# PowerSequence.net
KiCad netlist of a schematic drawn in Altium Designer
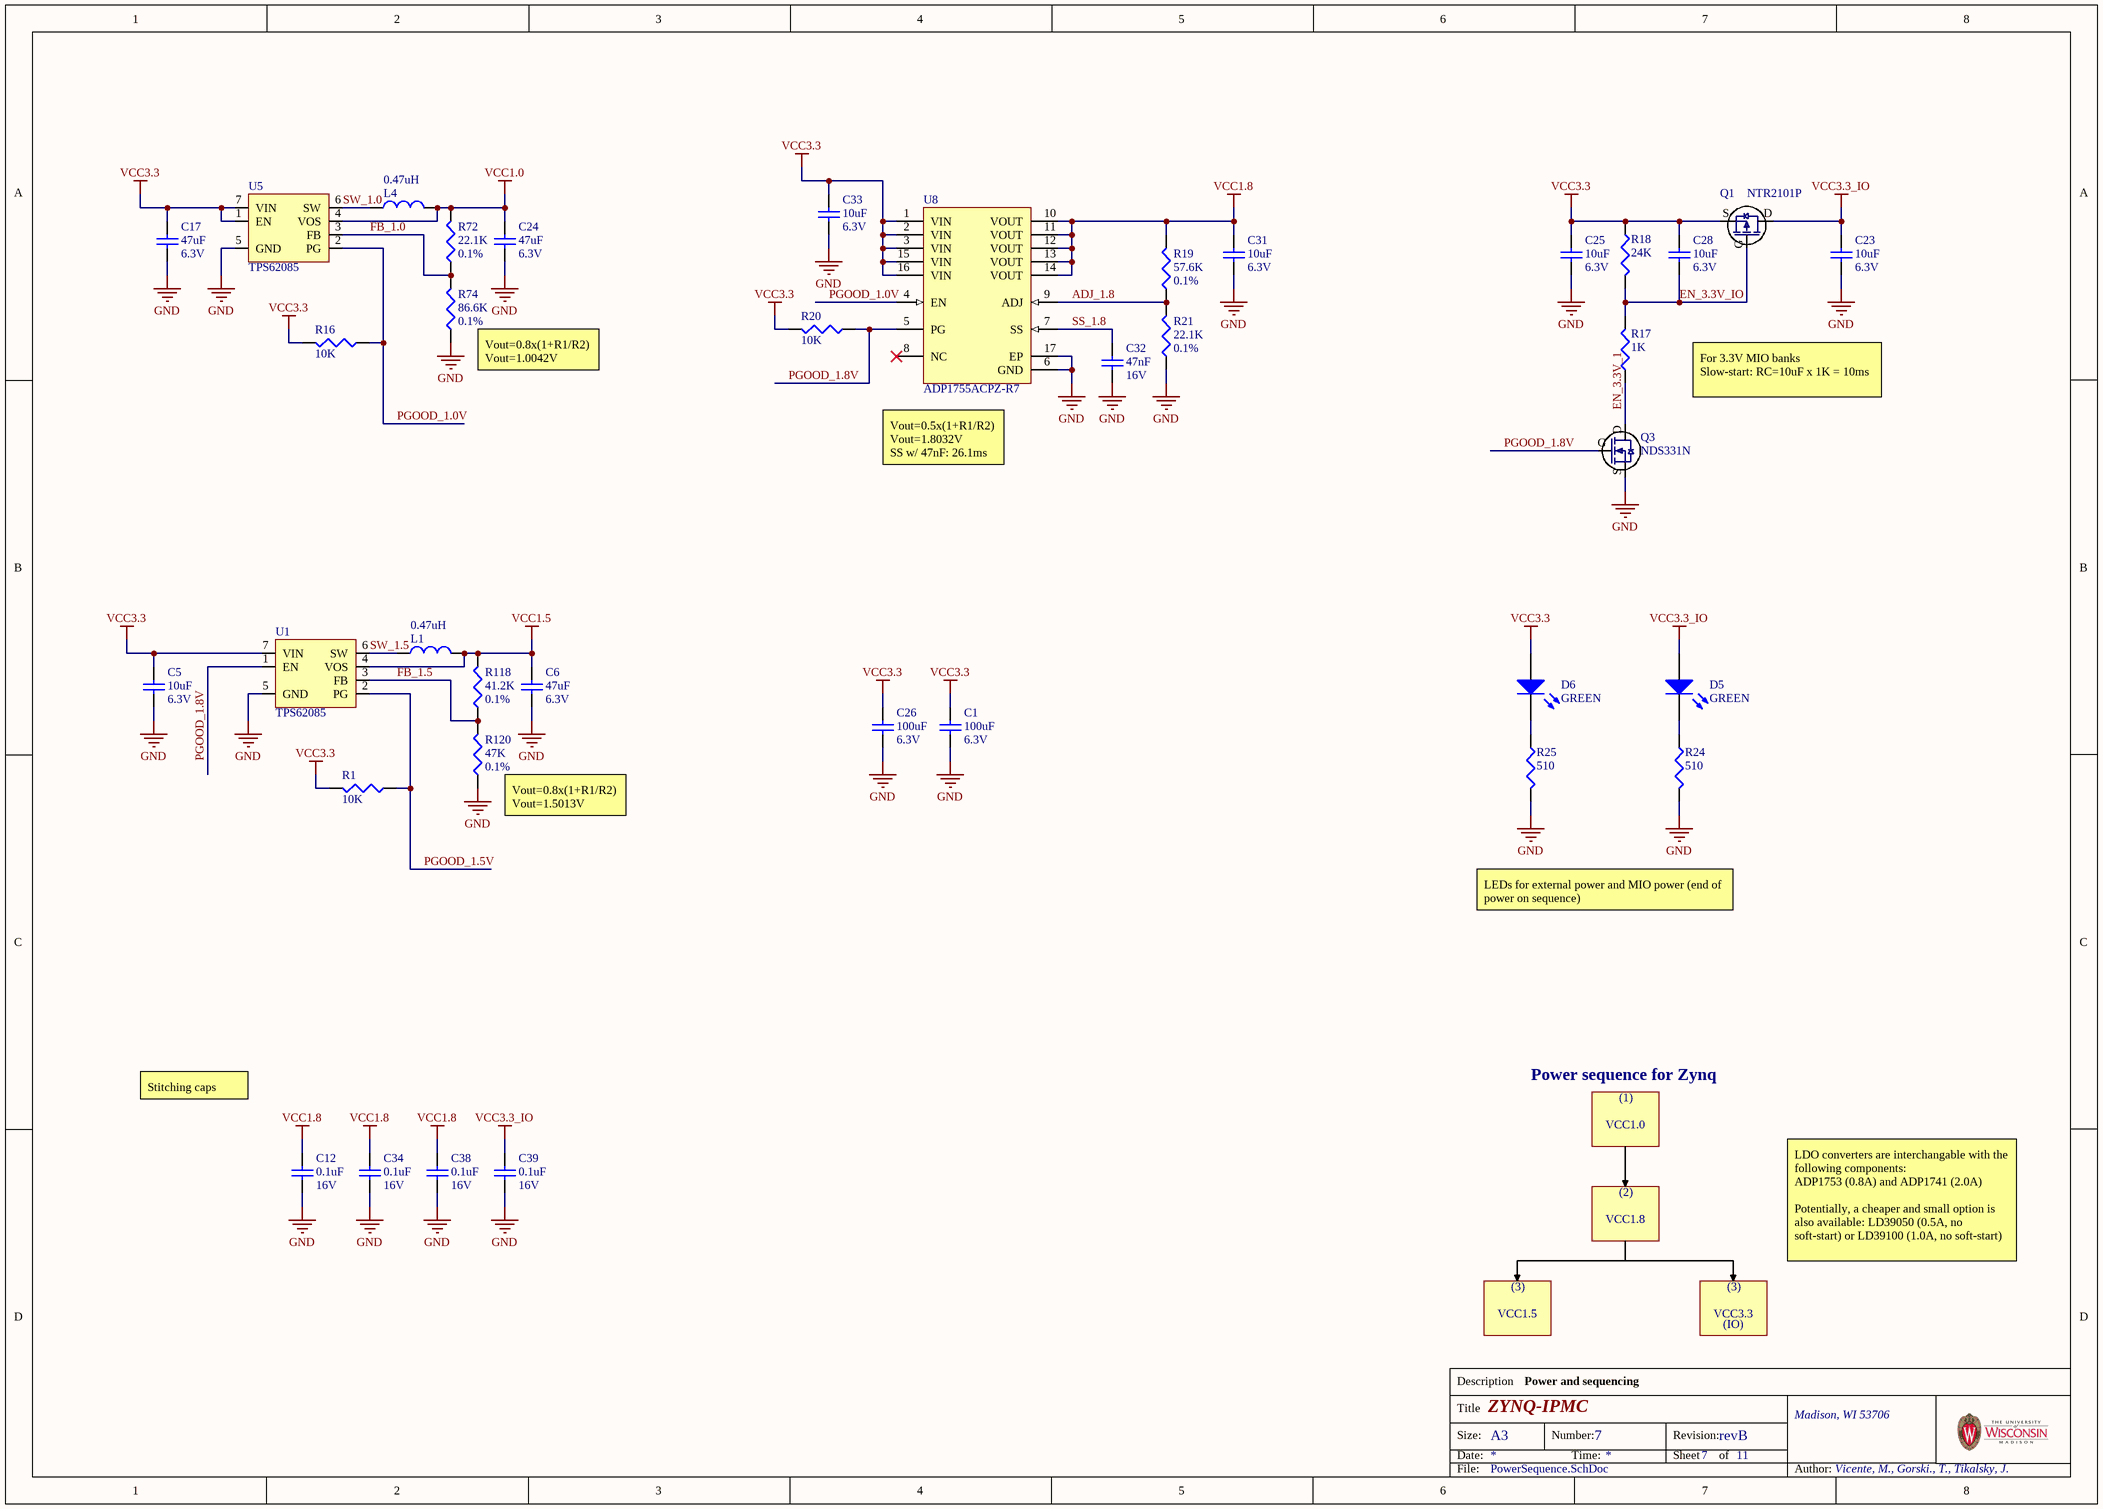
[diagram p0: PowerSequence.SchDoc]

(export (version "E")
  (design (tool "Eeschema 10.0.6"))
  (components
    (comp (ref "C1")
      (value "100uF")
      (footprint "C1210_IPC_H")
      (description "Capacitor")
      (fields
        (field (name "RATING") "6.3V")
        (field (name "PART") "GRM32ER60J107ME20L")
        (field (name "MANUFACTURER") "Murata")
      )
      (libsource (lib "CustomParts") (part "Cap"))
    )
    (comp (ref "C5")
      (value "10uF")
      (footprint "C0402_IPC_H")
      (description "Capacitor")
      (fields
        (field (name "RATING") "6.3V")
        (field (name "MANUFACTURER") "Murata")
        (field (name "PART") "GRM155R60J106ME44D")
      )
      (libsource (lib "CustomParts") (part "Cap"))
    )
    (comp (ref "C6")
      (value "47uF")
      (footprint "C0805_M")
      (description "Capacitor")
      (fields
        (field (name "RATING") "6.3V")
        (field (name "MANUFACTURER") "TDK")
        (field (name "PART") "C2012X5R0J476M125AC")
      )
      (libsource (lib "CustomParts") (part "Cap"))
    )
    (comp (ref "C12")
      (value "0.1uF")
      (footprint "C0402_IPC_H")
      (description "Capacitor")
      (fields
        (field (name "RATING") "16V")
        (field (name "MANUFACTURER") "Murata")
        (field (name "PART") "GRM155R71C104KA88D")
      )
      (libsource (lib "CustomParts") (part "Cap"))
    )
    (comp (ref "C17")
      (value "47uF")
      (footprint "C0805_M")
      (description "Capacitor")
      (fields
        (field (name "RATING") "6.3V")
        (field (name "MANUFACTURER") "TDK")
        (field (name "PART") "C2012X5R0J476M125AC")
      )
      (libsource (lib "CustomParts") (part "Cap"))
    )
    (comp (ref "C23")
      (value "10uF")
      (footprint "C0402_IPC_H")
      (description "Capacitor")
      (fields
        (field (name "RATING") "6.3V")
        (field (name "MANUFACTURER") "Murata")
        (field (name "PART") "GRM155R60J106ME44D")
      )
      (libsource (lib "CustomParts") (part "Cap"))
    )
    (comp (ref "C24")
      (value "47uF")
      (footprint "C0805_M")
      (description "Capacitor")
      (fields
        (field (name "RATING") "6.3V")
        (field (name "MANUFACTURER") "TDK")
        (field (name "PART") "C2012X5R0J476M125AC")
      )
      (libsource (lib "CustomParts") (part "Cap"))
    )
    (comp (ref "C25")
      (value "10uF")
      (footprint "C0402_IPC_H")
      (description "Capacitor")
      (fields
        (field (name "RATING") "6.3V")
        (field (name "MANUFACTURER") "Murata")
        (field (name "PART") "GRM155R60J106ME44D")
      )
      (libsource (lib "CustomParts") (part "Cap"))
    )
    (comp (ref "C26")
      (value "100uF")
      (footprint "C1210_IPC_H")
      (description "Capacitor")
      (fields
        (field (name "RATING") "6.3V")
        (field (name "PART") "GRM32ER60J107ME20L")
        (field (name "MANUFACTURER") "Murata")
      )
      (libsource (lib "CustomParts") (part "Cap"))
    )
    (comp (ref "C28")
      (value "10uF")
      (footprint "C0402_IPC_H")
      (description "Capacitor")
      (fields
        (field (name "RATING") "6.3V")
        (field (name "MANUFACTURER") "Murata")
        (field (name "PART") "GRM155R60J106ME44D")
      )
      (libsource (lib "CustomParts") (part "Cap"))
    )
    (comp (ref "C31")
      (value "10uF")
      (footprint "C0402_IPC_H")
      (description "Capacitor")
      (fields
        (field (name "RATING") "6.3V")
        (field (name "MANUFACTURER") "Murata")
        (field (name "PART") "GRM155R60J106ME44D")
      )
      (libsource (lib "CustomParts") (part "Cap"))
    )
    (comp (ref "C32")
      (value "47nF")
      (footprint "C0402_IPC_H")
      (description "Capacitor")
      (fields
        (field (name "RATING") "16V")
        (field (name "PART") "GRM155R71C473KA01D")
        (field (name "MANUFACTURER") "Murata")
      )
      (libsource (lib "CustomParts") (part "Cap"))
    )
    (comp (ref "C33")
      (value "10uF")
      (footprint "C0402_IPC_H")
      (description "Capacitor")
      (fields
        (field (name "RATING") "6.3V")
        (field (name "MANUFACTURER") "Murata")
        (field (name "PART") "GRM155R60J106ME44D")
      )
      (libsource (lib "CustomParts") (part "Cap"))
    )
    (comp (ref "C34")
      (value "0.1uF")
      (footprint "C0402_IPC_H")
      (description "Capacitor")
      (fields
        (field (name "RATING") "16V")
        (field (name "MANUFACTURER") "Murata")
        (field (name "PART") "GRM155R71C104KA88D")
      )
      (libsource (lib "CustomParts") (part "Cap"))
    )
    (comp (ref "C38")
      (value "0.1uF")
      (footprint "C0402_IPC_H")
      (description "Capacitor")
      (fields
        (field (name "RATING") "16V")
        (field (name "MANUFACTURER") "Murata")
        (field (name "PART") "GRM155R71C104KA88D")
      )
      (libsource (lib "CustomParts") (part "Cap"))
    )
    (comp (ref "C39")
      (value "0.1uF")
      (footprint "C0402_IPC_H")
      (description "Capacitor")
      (fields
        (field (name "RATING") "16V")
        (field (name "MANUFACTURER") "Murata")
        (field (name "PART") "GRM155R71C104KA88D")
      )
      (libsource (lib "CustomParts") (part "Cap"))
    )
    (comp (ref "D5")
      (value "GREEN")
      (footprint "LED0603_M")
      (description "Light Emitting Diode")
      (fields (field (name "MANUFACTURER") "Lite-On") (field (name "PART") "LTST-C190KGKT"))
      (libsource (lib "CustomParts") (part "LED"))
    )
    (comp (ref "D6")
      (value "GREEN")
      (footprint "LED0603_M")
      (description "Light Emitting Diode")
      (fields (field (name "MANUFACTURER") "Lite-On") (field (name "PART") "LTST-C190KGKT"))
      (libsource (lib "CustomParts") (part "LED"))
    )
    (comp (ref "L1")
      (value "0.47uH")
      (footprint "L2520_H")
      (description "Inductor")
      (fields (field (name "TOLERANCE") "20%") (field (name "MANUFACTURER") "Murata"))
      (libsource (lib "CustomParts") (part "Ind"))
    )
    (comp (ref "L4")
      (value "0.47uH")
      (footprint "L2520_H")
      (description "Inductor")
      (fields (field (name "TOLERANCE") "20%") (field (name "MANUFACTURER") "Murata"))
      (libsource (lib "CustomParts") (part "Ind"))
    )
    (comp (ref "Q1")
      (value "NTR2101P")
      (footprint "SOT23-H")
      (description "Small Signal MOSFET, −8.0V, −3.7 A, Single P−Channel, SOT−23")
      (fields (field (name "MANUFACTURER") "On Semiconductor"))
      (libsource (lib "CustomParts") (part "NTR2101P"))
    )
    (comp (ref "Q3")
      (value "NDS331N")
      (footprint "SOT23-H")
      (description "N-Channel   Logic Level Enhancement Mode Field Effect Transistor")
      (fields (field (name "MANUFACTURER") "Fairchild"))
      (libsource (lib "CustomParts") (part "NDS331N"))
    )
    (comp (ref "R1")
      (value "10K")
      (footprint "R0201_IPC_H")
      (description "Resistor")
      (fields (field (name "TOLERANCE") "1%") (field (name "MANUFACTURER") "Panasonic"))
      (libsource (lib "CustomParts") (part "Res"))
    )
    (comp (ref "R16")
      (value "10K")
      (footprint "R0201_IPC_H")
      (description "Resistor")
      (fields (field (name "TOLERANCE") "1%") (field (name "MANUFACTURER") "Panasonic"))
      (libsource (lib "CustomParts") (part "Res"))
    )
    (comp (ref "R17")
      (value "1K")
      (footprint "R0402_IPC_H")
      (description "Resistor")
      (fields (field (name "TOLERANCE") "1%") (field (name "MANUFACTURER") "Panasonic-ECG"))
      (libsource (lib "CustomParts") (part "Res"))
    )
    (comp (ref "R18")
      (value "24K")
      (footprint "R0402_IPC_H")
      (description "Resistor")
      (fields (field (name "TOLERANCE") "1%") (field (name "MANUFACTURER") "Panasonic"))
      (libsource (lib "CustomParts") (part "Res"))
    )
    (comp (ref "R19")
      (value "57.6K")
      (footprint "R0402_IPC_H")
      (description "Resistor")
      (fields
        (field (name "TOLERANCE") "0.1%")
        (field (name "MANUFACTURER") "Panasonic")
        (field (name "PART") "ERA-2AEB5762X")
      )
      (libsource (lib "CustomParts") (part "Res"))
    )
    (comp (ref "R20")
      (value "10K")
      (footprint "R0201_IPC_H")
      (description "Resistor")
      (fields (field (name "TOLERANCE") "1%") (field (name "MANUFACTURER") "Panasonic"))
      (libsource (lib "CustomParts") (part "Res"))
    )
    (comp (ref "R21")
      (value "22.1K")
      (footprint "R0402_IPC_H")
      (description "Resistor")
      (fields
        (field (name "TOLERANCE") "0.1%")
        (field (name "MANUFACTURER") "Panasonic")
        (field (name "PART") "ERA-2AEB2212X")
      )
      (libsource (lib "CustomParts") (part "Res"))
    )
    (comp (ref "R24")
      (value "510")
      (footprint "R0402_IPC_H")
      (description "Resistor")
      (fields (field (name "TOLERANCE") "1%") (field (name "MANUFACTURER") "Panasonic-ECG"))
      (libsource (lib "CustomParts") (part "Res"))
    )
    (comp (ref "R25")
      (value "510")
      (footprint "R0402_IPC_H")
      (description "Resistor")
      (fields (field (name "TOLERANCE") "1%") (field (name "MANUFACTURER") "Panasonic-ECG"))
      (libsource (lib "CustomParts") (part "Res"))
    )
    (comp (ref "R72")
      (value "22.1K")
      (footprint "R0402_IPC_H")
      (description "Resistor")
      (fields
        (field (name "TOLERANCE") "0.1%")
        (field (name "MANUFACTURER") "Panasonic")
        (field (name "PART") "ERA-2AEB2212X")
      )
      (libsource (lib "CustomParts") (part "Res"))
    )
    (comp (ref "R74")
      (value "86.6K")
      (footprint "R0402_IPC_H")
      (description "Resistor")
      (fields
        (field (name "TOLERANCE") "0.1%")
        (field (name "MANUFACTURER") "Panasonic-ECG")
        (field (name "PART") "ERA-2AEB8662X")
      )
      (libsource (lib "CustomParts") (part "Res"))
    )
    (comp (ref "R118")
      (value "41.2K")
      (footprint "R0402_IPC_H")
      (description "Resistor")
      (fields
        (field (name "TOLERANCE") "0.1%")
        (field (name "MANUFACTURER") "Panasonic")
        (field (name "PART") "ERA-2AEB4122X")
      )
      (libsource (lib "CustomParts") (part "Res"))
    )
    (comp (ref "R120")
      (value "47K")
      (footprint "R0402_IPC_H")
      (description "Resistor")
      (fields
        (field (name "TOLERANCE") "0.1%")
        (field (name "MANUFACTURER") "Panasonic")
        (field (name "PART") "ERA-2AEB473X")
      )
      (libsource (lib "CustomParts") (part "Res"))
    )
    (comp (ref "U1")
      (value "TPS62085")
      (footprint "VSON-8_L")
      (description "3-A Step-Down Converter With Hiccup Short-Circuit Protection")
      (fields (field (name "MANUFACTURER") "Texas Instruments"))
      (libsource (lib "CustomParts") (part "TPS62085"))
    )
    (comp (ref "U5")
      (value "TPS62085")
      (footprint "VSON-8_L")
      (description "3-A Step-Down Converter With Hiccup Short-Circuit Protection")
      (fields (field (name "MANUFACTURER") "Texas Instruments"))
      (libsource (lib "CustomParts") (part "TPS62085"))
    )
    (comp (ref "U8")
      (value "ADP1755ACPZ-R7")
      (footprint "CP-16-4_L")
      (fields (field (name "MANUFACTURER") "Analog"))
      (libsource (lib "altium-import") (part "root_0_ADI-ADP1755-CP-16-4_"))
    )
  )
  (nets
    (net (code "1") (name "/ADJ_1.8") (class "Default")
      (node (ref "R19") (pin "1") (pinfunction "1_1") (pintype "passive"))
      (node (ref "R21") (pin "2") (pinfunction "2_2") (pintype "passive"))
      (node (ref "U8") (pin "9") (pinfunction "ADJ_9") (pintype "input"))
    )
    (net (code "2") (name "/EN_3.3V_1") (class "Default")
      (node (ref "Q3") (pin "D") (pinfunction "D_D") (pintype "passive"))
      (node (ref "R17") (pin "1") (pinfunction "1_1") (pintype "passive"))
    )
    (net (code "3") (name "/EN_3.3V_IO") (class "Default")
      (node (ref "C28") (pin "2") (pinfunction "2_2") (pintype "passive"))
      (node (ref "Q1") (pin "G") (pinfunction "G_G") (pintype "passive"))
      (node (ref "R17") (pin "2") (pinfunction "2_2") (pintype "passive"))
      (node (ref "R18") (pin "2") (pinfunction "2_2") (pintype "passive"))
    )
    (net (code "4") (name "/FB_1.0") (class "Default")
      (node (ref "R72") (pin "1") (pinfunction "1_1") (pintype "passive"))
      (node (ref "R74") (pin "2") (pinfunction "2_2") (pintype "passive"))
      (node (ref "U5") (pin "3") (pinfunction "FB_3") (pintype "passive"))
    )
    (net (code "5") (name "/FB_1.5") (class "Default")
      (node (ref "R118") (pin "1") (pinfunction "1_1") (pintype "passive"))
      (node (ref "R120") (pin "2") (pinfunction "2_2") (pintype "passive"))
      (node (ref "U1") (pin "3") (pinfunction "FB_3") (pintype "passive"))
    )
    (net (code "6") (name "/PGOOD_1.0V") (class "Default")
      (node (ref "R16") (pin "1") (pinfunction "1_1") (pintype "passive"))
      (node (ref "U5") (pin "2") (pinfunction "PG_2") (pintype "passive"))
      (node (ref "U8") (pin "4") (pinfunction "EN_4") (pintype "input"))
    )
    (net (code "7") (name "/PGOOD_1.5V") (class "Default")
      (node (ref "R1") (pin "1") (pinfunction "1_1") (pintype "passive"))
      (node (ref "U1") (pin "2") (pinfunction "PG_2") (pintype "passive"))
    )
    (net (code "8") (name "/PGOOD_1.8V") (class "Default")
      (node (ref "Q3") (pin "G") (pinfunction "G_G") (pintype "passive"))
      (node (ref "R20") (pin "1") (pinfunction "1_1") (pintype "passive"))
      (node (ref "U1") (pin "1") (pinfunction "EN_1") (pintype "passive"))
      (node (ref "U8") (pin "5") (pinfunction "PG_5") (pintype "open_collector"))
    )
    (net (code "9") (name "/SS_1.8") (class "Default")
      (node (ref "C32") (pin "1") (pinfunction "1_1") (pintype "passive"))
      (node (ref "U8") (pin "7") (pinfunction "SS_7") (pintype "input"))
    )
    (net (code "10") (name "/SW_1.0") (class "Default")
      (node (ref "L4") (pin "1") (pinfunction "1_1") (pintype "passive"))
      (node (ref "U5") (pin "6") (pinfunction "SW_6") (pintype "passive"))
    )
    (net (code "11") (name "/SW_1.5") (class "Default")
      (node (ref "L1") (pin "1") (pinfunction "1_1") (pintype "passive"))
      (node (ref "U1") (pin "6") (pinfunction "SW_6") (pintype "passive"))
    )
    (net (code "12") (name "GND") (class "Default")
      (node (ref "C1") (pin "2") (pinfunction "2_2") (pintype "passive"))
      (node (ref "C12") (pin "2") (pinfunction "2_2") (pintype "passive"))
      (node (ref "C17") (pin "2") (pinfunction "2_2") (pintype "passive"))
      (node (ref "C23") (pin "2") (pinfunction "2_2") (pintype "passive"))
      (node (ref "C24") (pin "1") (pinfunction "1_1") (pintype "passive"))
      (node (ref "C25") (pin "2") (pinfunction "2_2") (pintype "passive"))
      (node (ref "C26") (pin "2") (pinfunction "2_2") (pintype "passive"))
      (node (ref "C31") (pin "1") (pinfunction "1_1") (pintype "passive"))
      (node (ref "C32") (pin "2") (pinfunction "2_2") (pintype "passive"))
      (node (ref "C33") (pin "2") (pinfunction "2_2") (pintype "passive"))
      (node (ref "C34") (pin "2") (pinfunction "2_2") (pintype "passive"))
      (node (ref "C38") (pin "2") (pinfunction "2_2") (pintype "passive"))
      (node (ref "C39") (pin "2") (pinfunction "2_2") (pintype "passive"))
      (node (ref "C5") (pin "2") (pinfunction "2_2") (pintype "passive"))
      (node (ref "C6") (pin "1") (pinfunction "1_1") (pintype "passive"))
      (node (ref "Q3") (pin "S") (pinfunction "S_S") (pintype "passive"))
      (node (ref "R120") (pin "1") (pinfunction "1_1") (pintype "passive"))
      (node (ref "R21") (pin "1") (pinfunction "1_1") (pintype "passive"))
      (node (ref "R24") (pin "2") (pinfunction "2_2") (pintype "passive"))
      (node (ref "R25") (pin "2") (pinfunction "2_2") (pintype "passive"))
      (node (ref "R74") (pin "1") (pinfunction "1_1") (pintype "passive"))
      (node (ref "U1") (pin "5") (pinfunction "GND_5") (pintype "passive"))
      (node (ref "U5") (pin "5") (pinfunction "GND_5") (pintype "passive"))
      (node (ref "U8") (pin "17") (pinfunction "EP_17") (pintype "power_in"))
      (node (ref "U8") (pin "6") (pinfunction "GND_6") (pintype "power_in"))
    )
    (net (code "13") (name "Net-(D5-K)") (class "Default")
      (node (ref "D5") (pin "2") (pinfunction "K_2") (pintype "passive"))
      (node (ref "R24") (pin "1") (pinfunction "1_1") (pintype "passive"))
    )
    (net (code "14") (name "Net-(D6-K)") (class "Default")
      (node (ref "D6") (pin "2") (pinfunction "K_2") (pintype "passive"))
      (node (ref "R25") (pin "1") (pinfunction "1_1") (pintype "passive"))
    )
    (net (code "15") (name "VCC1.0") (class "Default")
      (node (ref "C24") (pin "2") (pinfunction "2_2") (pintype "passive"))
      (node (ref "L4") (pin "2") (pinfunction "2_2") (pintype "passive"))
      (node (ref "R72") (pin "2") (pinfunction "2_2") (pintype "passive"))
      (node (ref "U5") (pin "4") (pinfunction "VOS_4") (pintype "passive"))
    )
    (net (code "16") (name "VCC1.5") (class "Default")
      (node (ref "C6") (pin "2") (pinfunction "2_2") (pintype "passive"))
      (node (ref "L1") (pin "2") (pinfunction "2_2") (pintype "passive"))
      (node (ref "R118") (pin "2") (pinfunction "2_2") (pintype "passive"))
      (node (ref "U1") (pin "4") (pinfunction "VOS_4") (pintype "passive"))
    )
    (net (code "17") (name "VCC1.8") (class "Default")
      (node (ref "C12") (pin "1") (pinfunction "1_1") (pintype "passive"))
      (node (ref "C31") (pin "2") (pinfunction "2_2") (pintype "passive"))
      (node (ref "C34") (pin "1") (pinfunction "1_1") (pintype "passive"))
      (node (ref "C38") (pin "1") (pinfunction "1_1") (pintype "passive"))
      (node (ref "R19") (pin "2") (pinfunction "2_2") (pintype "passive"))
      (node (ref "U8") (pin "10") (pinfunction "VOUT_10") (pintype "power_in"))
      (node (ref "U8") (pin "11") (pinfunction "VOUT_11") (pintype "power_in"))
      (node (ref "U8") (pin "12") (pinfunction "VOUT_12") (pintype "power_in"))
      (node (ref "U8") (pin "13") (pinfunction "VOUT_13") (pintype "power_in"))
      (node (ref "U8") (pin "14") (pinfunction "VOUT_14") (pintype "power_in"))
    )
    (net (code "18") (name "VCC3.3") (class "Default")
      (node (ref "C1") (pin "1") (pinfunction "1_1") (pintype "passive"))
      (node (ref "C17") (pin "1") (pinfunction "1_1") (pintype "passive"))
      (node (ref "C25") (pin "1") (pinfunction "1_1") (pintype "passive"))
      (node (ref "C26") (pin "1") (pinfunction "1_1") (pintype "passive"))
      (node (ref "C28") (pin "1") (pinfunction "1_1") (pintype "passive"))
      (node (ref "C33") (pin "1") (pinfunction "1_1") (pintype "passive"))
      (node (ref "C5") (pin "1") (pinfunction "1_1") (pintype "passive"))
      (node (ref "D6") (pin "1") (pinfunction "A_1") (pintype "passive"))
      (node (ref "Q1") (pin "S") (pinfunction "S_S") (pintype "passive"))
      (node (ref "R1") (pin "2") (pinfunction "2_2") (pintype "passive"))
      (node (ref "R16") (pin "2") (pinfunction "2_2") (pintype "passive"))
      (node (ref "R18") (pin "1") (pinfunction "1_1") (pintype "passive"))
      (node (ref "R20") (pin "2") (pinfunction "2_2") (pintype "passive"))
      (node (ref "U1") (pin "7") (pinfunction "VIN_7") (pintype "passive"))
      (node (ref "U5") (pin "1") (pinfunction "EN_1") (pintype "passive"))
      (node (ref "U5") (pin "7") (pinfunction "VIN_7") (pintype "passive"))
      (node (ref "U8") (pin "1") (pinfunction "VIN_1") (pintype "power_in"))
      (node (ref "U8") (pin "15") (pinfunction "VIN_15") (pintype "power_in"))
      (node (ref "U8") (pin "16") (pinfunction "VIN_16") (pintype "power_in"))
      (node (ref "U8") (pin "2") (pinfunction "VIN_2") (pintype "power_in"))
      (node (ref "U8") (pin "3") (pinfunction "VIN_3") (pintype "power_in"))
    )
    (net (code "19") (name "VCC3.3_IO") (class "Default")
      (node (ref "C23") (pin "1") (pinfunction "1_1") (pintype "passive"))
      (node (ref "C39") (pin "1") (pinfunction "1_1") (pintype "passive"))
      (node (ref "D5") (pin "1") (pinfunction "A_1") (pintype "passive"))
      (node (ref "Q1") (pin "D") (pinfunction "D_D") (pintype "passive"))
    )
    (net (code "20") (name "unconnected-(U8-NC-Pad8)") (class "Default")
      (node (ref "U8") (pin "8") (pinfunction "NC_8") (pintype "passive+no_connect"))
    )
  )
)
